# Schematic.net
KiCad netlist of a schematic drawn in Altium Designer
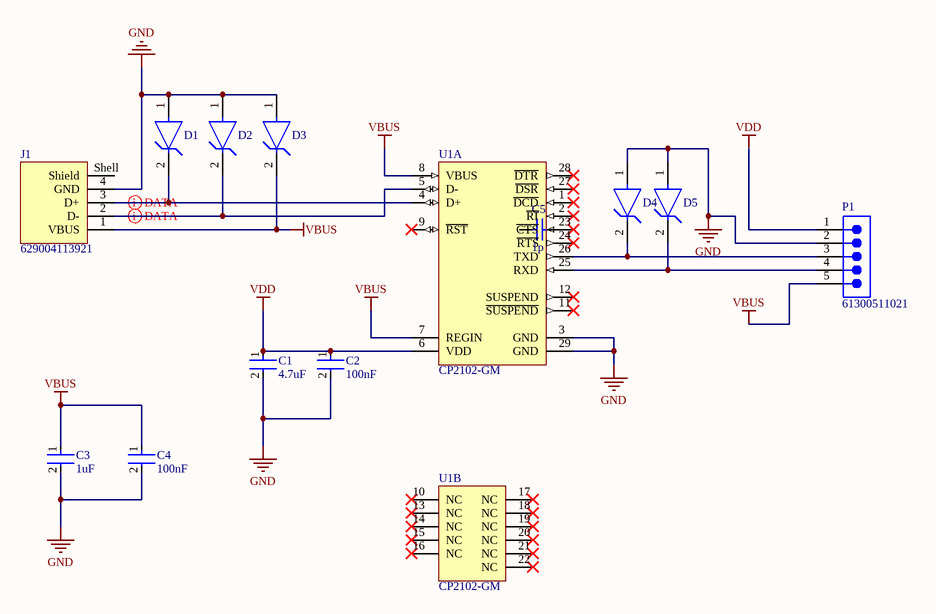
[diagram p0: Schematic.SchDoc]

(export (version "E")
  (design (tool "Eeschema 10.0.6"))
  (components
    (comp (ref "C1")
      (value "4.7uF")
      (footprint "FP-GRM155-0_1-IPC_B")
      (description "Chip Multilayer Ceramic Capacitors for General Purpose, 0402, 4.7uF, X5R, 15%, 20%, 6.3V")
      (fields (field (name "VOLTAGE") "6.3V") (field (name "TOLERANCE") "20%"))
      (libsource (lib "Altium Content Vault") (part "11868f565c42a9108669ba33697ecf6"))
    )
    (comp (ref "C2")
      (value "100nF")
      (footprint "FP-GRM033-0_03-MFG")
      (description "Chip Multilayer Ceramic Capacitors for General Purpose, 0201, 0.10uF, X5R, 15%, 10%, 6.3V")
      (fields (field (name "VOLTAGE") "6.3V") (field (name "TOLERANCE") "10%"))
      (libsource (lib "Altium Content Vault") (part "b4654b650e69147ec39a6b967a45e02"))
    )
    (comp (ref "C3")
      (value "1uF")
      (footprint "FP-GRM15-0_1-MFG")
      (description "CAP CER 1UF 10V X5R 0402")
      (fields
        (field (name "OCTOPART") "https://octopart.com/grm155r61a105ke15d-murata-197442")
        (field (name "MANUFACTURER PART NUMBER") "GRM155R61A105KE15D")
      )
      (libsource (lib "Altium Content Vault") (part "02cd4be3c70576c341d710602a673aa"))
    )
    (comp (ref "C4")
      (value "100nF")
      (footprint "FP-GRM033-0_03-MFG")
      (description "Chip Multilayer Ceramic Capacitors for General Purpose, 0201, 0.10uF, X5R, 15%, 10%, 6.3V")
      (fields (field (name "VOLTAGE") "6.3V") (field (name "TOLERANCE") "10%"))
      (libsource (lib "Altium Content Vault") (part "b4654b650e69147ec39a6b967a45e02"))
    )
    (comp (ref "C5")
      (value "1p")
      (description "Capacitor")
      (libsource (lib "Simulation Generic Components") (part "Capacitor"))
    )
    (comp (ref "D1")
      (value "UCLAMP3601P.TNT")
      (footprint "FP-SLP1006P2-MFG")
      (description "TVS DIODE 33VWM 60VC SLP1006P2")
      (libsource (lib "Altium Content Vault") (part "3fba79ac723ca0a4e69928609483429"))
    )
    (comp (ref "D2")
      (value "UCLAMP3601P.TNT")
      (footprint "FP-SLP1006P2-MFG")
      (description "TVS DIODE 33VWM 60VC SLP1006P2")
      (libsource (lib "Altium Content Vault") (part "3fba79ac723ca0a4e69928609483429"))
    )
    (comp (ref "D3")
      (value "UCLAMP3601P.TNT")
      (footprint "FP-SLP1006P2-MFG")
      (description "TVS DIODE 33VWM 60VC SLP1006P2")
      (libsource (lib "Altium Content Vault") (part "3fba79ac723ca0a4e69928609483429"))
    )
    (comp (ref "D4")
      (value "UCLAMP3601P.TNT")
      (footprint "FP-SLP1006P2-MFG")
      (description "TVS DIODE 33VWM 60VC SLP1006P2")
      (libsource (lib "Altium Content Vault") (part "3fba79ac723ca0a4e69928609483429"))
    )
    (comp (ref "D5")
      (value "UCLAMP3601P.TNT")
      (footprint "FP-SLP1006P2-MFG")
      (description "TVS DIODE 33VWM 60VC SLP1006P2")
      (libsource (lib "Altium Content Vault") (part "3fba79ac723ca0a4e69928609483429"))
    )
    (comp (ref "J1")
      (value "629004113921")
      (footprint "629004113921")
      (libsource (lib "Altium Content Vault") (part "USB 2.0_Type A_Plug_1 Port"))
    )
    (comp (ref "P1")
      (value "61300511021")
      (footprint "61300511021")
      (libsource (lib "Altium Content Vault") (part "Header_Male_1R_05P"))
    )
    (comp (ref "U1")
      (value "CP2102-GM")
      (footprint "SLAB-QFN-28-3125x3125TP_N")
      (description "Single-Chip USB to UART Bridge, 1024 Bytes EEPROM, -40 to 85 degC, 28-pin QFN, Tube")
      (fields (field (name "MANUFACTURER") "Silicon Labs"))
      (libsource (lib "Altium Content Vault") (part "SLAB-CP210X-QFN-28-29"))
    )
  )
  (nets
    (net (code "1") (name "GND") (class "Default")
      (node (ref "C1") (pin "2") (pinfunction "2_2") (pintype "passive"))
      (node (ref "C2") (pin "2") (pinfunction "2_2") (pintype "passive"))
      (node (ref "C3") (pin "2") (pinfunction "2_2") (pintype "passive"))
      (node (ref "C4") (pin "2") (pinfunction "2_2") (pintype "passive"))
      (node (ref "D1") (pin "1") (pinfunction "A_1") (pintype "passive"))
      (node (ref "D2") (pin "1") (pinfunction "A_1") (pintype "passive"))
      (node (ref "D3") (pin "1") (pinfunction "A_1") (pintype "passive"))
      (node (ref "D4") (pin "1") (pinfunction "A_1") (pintype "passive"))
      (node (ref "D5") (pin "1") (pinfunction "A_1") (pintype "passive"))
      (node (ref "J1") (pin "4") (pinfunction "GND_4") (pintype "passive"))
      (node (ref "P1") (pin "2") (pinfunction "2_2") (pintype "passive"))
      (node (ref "U1") (pin "29") (pinfunction "GND_29") (pintype "power_in"))
      (node (ref "U1") (pin "3") (pinfunction "GND_3") (pintype "power_in"))
    )
    (net (code "2") (name "Net-(D1-C)") (class "Default")
      (node (ref "D1") (pin "2") (pinfunction "C_2") (pintype "passive"))
      (node (ref "J1") (pin "3") (pinfunction "D+_3") (pintype "passive"))
      (node (ref "U1") (pin "4") (pinfunction "D+_4") (pintype "bidirectional"))
    )
    (net (code "3") (name "Net-(D2-C)") (class "Default")
      (node (ref "D2") (pin "2") (pinfunction "C_2") (pintype "passive"))
      (node (ref "J1") (pin "2") (pinfunction "D-_2") (pintype "passive"))
      (node (ref "U1") (pin "5") (pinfunction "D-_5") (pintype "bidirectional"))
    )
    (net (code "4") (name "Net-(D4-C)") (class "Default")
      (node (ref "D4") (pin "2") (pinfunction "C_2") (pintype "passive"))
      (node (ref "P1") (pin "3") (pinfunction "3_3") (pintype "passive"))
      (node (ref "U1") (pin "26") (pinfunction "TXD_26") (pintype "output"))
    )
    (net (code "5") (name "Net-(D5-C)") (class "Default")
      (node (ref "D5") (pin "2") (pinfunction "C_2") (pintype "passive"))
      (node (ref "P1") (pin "4") (pinfunction "4_4") (pintype "passive"))
      (node (ref "U1") (pin "25") (pinfunction "RXD_25") (pintype "input"))
    )
    (net (code "6") (name "VBUS") (class "Default")
      (node (ref "C3") (pin "1") (pinfunction "1_1") (pintype "passive"))
      (node (ref "C4") (pin "1") (pinfunction "1_1") (pintype "passive"))
      (node (ref "D3") (pin "2") (pinfunction "C_2") (pintype "passive"))
      (node (ref "J1") (pin "1") (pinfunction "VBUS_1") (pintype "passive"))
      (node (ref "P1") (pin "5") (pinfunction "5_5") (pintype "passive"))
      (node (ref "U1") (pin "7") (pinfunction "REGIN_7") (pintype "power_in"))
      (node (ref "U1") (pin "8") (pinfunction "VBUS_8") (pintype "input"))
    )
    (net (code "7") (name "VDD") (class "Default")
      (node (ref "C1") (pin "1") (pinfunction "1_1") (pintype "passive"))
      (node (ref "C2") (pin "1") (pinfunction "1_1") (pintype "passive"))
      (node (ref "P1") (pin "1") (pinfunction "1_1") (pintype "passive"))
      (node (ref "U1") (pin "6") (pinfunction "VDD_6") (pintype "power_in"))
    )
    (net (code "8") (name "unconnected-(C5-Pad1)") (class "Default")
      (node (ref "C5") (pin "1") (pinfunction "1_1") (pintype "passive"))
    )
    (net (code "9") (name "unconnected-(C5-Pad2)") (class "Default")
      (node (ref "C5") (pin "2") (pinfunction "2_2") (pintype "passive"))
    )
    (net (code "10") (name "unconnected-(J1-Shield-PadShell)") (class "Default")
      (node (ref "J1") (pin "Shell") (pinfunction "Shield_Shell") (pintype "passive"))
    )
    (net (code "11") (name "unconnected-(U1A-SUSPEND-Pad12)") (class "Default")
      (node (ref "U1") (pin "12") (pinfunction "SUSPEND_12") (pintype "output+no_connect"))
    )
    (net (code "12") (name "unconnected-(U1A-~{CTS}-Pad23)") (class "Default")
      (node (ref "U1") (pin "23") (pinfunction "~{CTS}_23") (pintype "input+no_connect"))
    )
    (net (code "13") (name "unconnected-(U1A-~{DCD}-Pad1)") (class "Default")
      (node (ref "U1") (pin "1") (pinfunction "~{DCD}_1") (pintype "input+no_connect"))
    )
    (net (code "14") (name "unconnected-(U1A-~{DSR}-Pad27)") (class "Default")
      (node (ref "U1") (pin "27") (pinfunction "~{DSR}_27") (pintype "input+no_connect"))
    )
    (net (code "15") (name "unconnected-(U1A-~{DTR}-Pad28)") (class "Default")
      (node (ref "U1") (pin "28") (pinfunction "~{DTR}_28") (pintype "output+no_connect"))
    )
    (net (code "16") (name "unconnected-(U1A-~{RI}-Pad2)") (class "Default")
      (node (ref "U1") (pin "2") (pinfunction "~{RI}_2") (pintype "input+no_connect"))
    )
    (net (code "17") (name "unconnected-(U1A-~{RST}-Pad9)") (class "Default")
      (node (ref "U1") (pin "9") (pinfunction "~{RST}_9") (pintype "bidirectional+no_connect"))
    )
    (net (code "18") (name "unconnected-(U1A-~{RTS}-Pad24)") (class "Default")
      (node (ref "U1") (pin "24") (pinfunction "~{RTS}_24") (pintype "output+no_connect"))
    )
    (net (code "19") (name "unconnected-(U1A-~{SUSPEND}-Pad11)") (class "Default")
      (node (ref "U1") (pin "11") (pinfunction "~{SUSPEND}_11") (pintype "output+no_connect"))
    )
    (net (code "20") (name "unconnected-(U1B-NC-Pad10)") (class "Default")
      (node (ref "U1") (pin "10") (pinfunction "NC_10") (pintype "passive+no_connect"))
    )
    (net (code "21") (name "unconnected-(U1B-NC-Pad13)") (class "Default")
      (node (ref "U1") (pin "13") (pinfunction "NC_13") (pintype "passive+no_connect"))
    )
    (net (code "22") (name "unconnected-(U1B-NC-Pad14)") (class "Default")
      (node (ref "U1") (pin "14") (pinfunction "NC_14") (pintype "passive+no_connect"))
    )
    (net (code "23") (name "unconnected-(U1B-NC-Pad15)") (class "Default")
      (node (ref "U1") (pin "15") (pinfunction "NC_15") (pintype "passive+no_connect"))
    )
    (net (code "24") (name "unconnected-(U1B-NC-Pad16)") (class "Default")
      (node (ref "U1") (pin "16") (pinfunction "NC_16") (pintype "passive+no_connect"))
    )
    (net (code "25") (name "unconnected-(U1B-NC-Pad17)") (class "Default")
      (node (ref "U1") (pin "17") (pinfunction "NC_17") (pintype "passive+no_connect"))
    )
    (net (code "26") (name "unconnected-(U1B-NC-Pad18)") (class "Default")
      (node (ref "U1") (pin "18") (pinfunction "NC_18") (pintype "passive+no_connect"))
    )
    (net (code "27") (name "unconnected-(U1B-NC-Pad19)") (class "Default")
      (node (ref "U1") (pin "19") (pinfunction "NC_19") (pintype "passive+no_connect"))
    )
    (net (code "28") (name "unconnected-(U1B-NC-Pad20)") (class "Default")
      (node (ref "U1") (pin "20") (pinfunction "NC_20") (pintype "passive+no_connect"))
    )
    (net (code "29") (name "unconnected-(U1B-NC-Pad21)") (class "Default")
      (node (ref "U1") (pin "21") (pinfunction "NC_21") (pintype "passive+no_connect"))
    )
    (net (code "30") (name "unconnected-(U1B-NC-Pad22)") (class "Default")
      (node (ref "U1") (pin "22") (pinfunction "NC_22") (pintype "passive+no_connect"))
    )
  )
)
